# Tile0.net
KiCad netlist of a schematic drawn in Altium Designer
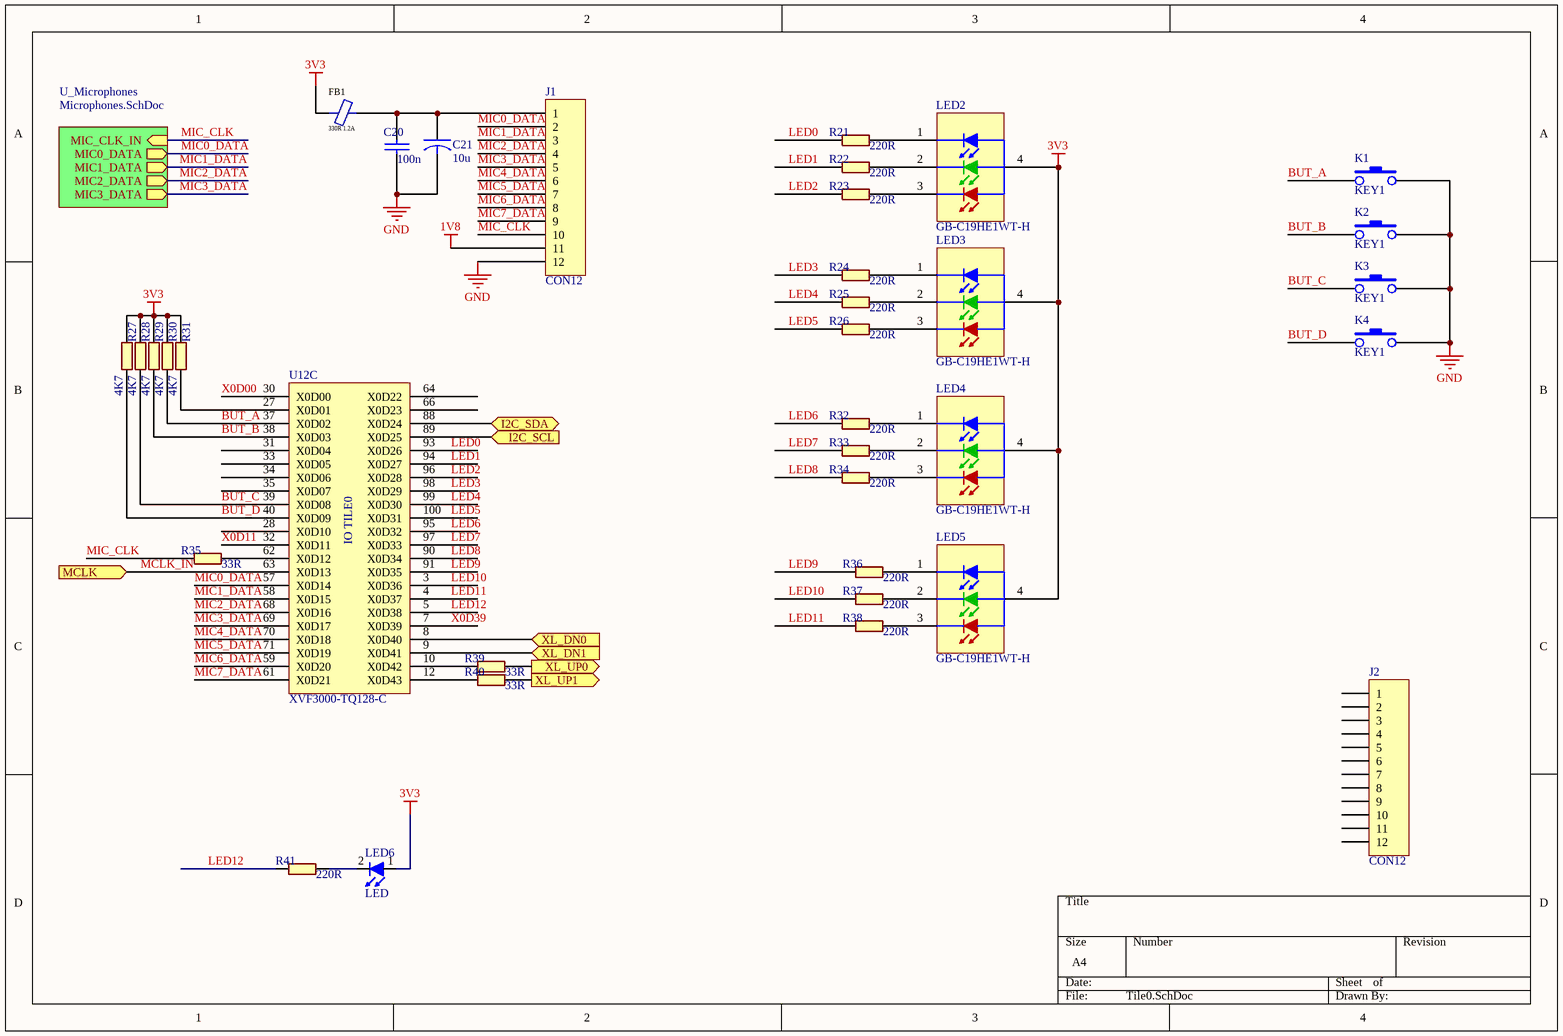
[diagram p0: Tile0.SchDoc]

(export (version "E")
  (design (tool "Eeschema 10.0.6"))
  (components
    (comp (ref "C20")
      (value "100n")
      (footprint "C0603")
      (description "Capacitor")
      (libsource (lib "Library") (part "CAP"))
    )
    (comp (ref "C21")
      (value "10u")
      (footprint "C1206")
      (description "Capacitor")
      (libsource (lib "Library") (part "CAPACITOR"))
    )
    (comp (ref "FB1") (value "330R 1.2A") (footprint "L0603") (libsource (lib "Library") (part "FB")))
    (comp (ref "J1")
      (value "CON12")
      (footprint "FFC/SM0.5-2H12A")
      (description "Connector")
      (libsource (lib "Library") (part "CON12"))
    )
    (comp (ref "J2")
      (value "CON12")
      (footprint "FFC/SM0.5-2H12A")
      (description "Connector")
      (libsource (lib "Library") (part "CON12"))
    )
    (comp (ref "K1")
      (value "KEY1")
      (footprint "BUTTON6")
      (description "BUTTON")
      (libsource (lib "Library") (part "BUTTON"))
    )
    (comp (ref "K2")
      (value "KEY1")
      (footprint "BUTTON6")
      (description "BUTTON")
      (libsource (lib "Library") (part "BUTTON"))
    )
    (comp (ref "K3")
      (value "KEY1")
      (footprint "BUTTON6")
      (description "BUTTON")
      (libsource (lib "Library") (part "BUTTON"))
    )
    (comp (ref "K4")
      (value "KEY1")
      (footprint "BUTTON6")
      (description "BUTTON")
      (libsource (lib "Library") (part "BUTTON"))
    )
    (comp (ref "LED2")
      (value "GB-C19HE1WT-H")
      (footprint "LED1615")
      (description "LED RGB")
      (libsource (lib "Library") (part "LED-1615"))
    )
    (comp (ref "LED3")
      (value "GB-C19HE1WT-H")
      (footprint "LED1615")
      (description "LED RGB")
      (libsource (lib "Library") (part "LED-1615"))
    )
    (comp (ref "LED4")
      (value "GB-C19HE1WT-H")
      (footprint "LED1615")
      (description "LED RGB")
      (libsource (lib "Library") (part "LED-1615"))
    )
    (comp (ref "LED5")
      (value "GB-C19HE1WT-H")
      (footprint "LED1615")
      (description "LED RGB")
      (libsource (lib "Library") (part "LED-1615"))
    )
    (comp (ref "LED6") (value "LED") (footprint "LED0805") (libsource (lib "Library") (part "LED")))
    (comp (ref "R21")
      (value "220R")
      (footprint "R0603")
      (description "RES")
      (libsource (lib "Library") (part "R"))
    )
    (comp (ref "R22")
      (value "220R")
      (footprint "R0603")
      (description "RES")
      (libsource (lib "Library") (part "R"))
    )
    (comp (ref "R23")
      (value "220R")
      (footprint "R0603")
      (description "RES")
      (libsource (lib "Library") (part "R"))
    )
    (comp (ref "R24")
      (value "220R")
      (footprint "R0603")
      (description "RES")
      (libsource (lib "Library") (part "R"))
    )
    (comp (ref "R25")
      (value "220R")
      (footprint "R0603")
      (description "RES")
      (libsource (lib "Library") (part "R"))
    )
    (comp (ref "R26")
      (value "220R")
      (footprint "R0603")
      (description "RES")
      (libsource (lib "Library") (part "R"))
    )
    (comp (ref "R27") (value "4K7") (footprint "R0603") (description "RES") (libsource (lib "") (part "R_1")))
    (comp (ref "R28") (value "4K7") (footprint "R0603") (description "RES") (libsource (lib "") (part "R_1")))
    (comp (ref "R29") (value "4K7") (footprint "R0603") (description "RES") (libsource (lib "") (part "R_1")))
    (comp (ref "R30") (value "4K7") (footprint "R0603") (description "RES") (libsource (lib "") (part "R_1")))
    (comp (ref "R31") (value "4K7") (footprint "R0603") (description "RES") (libsource (lib "") (part "R_1")))
    (comp (ref "R32")
      (value "220R")
      (footprint "R0603")
      (description "RES")
      (libsource (lib "Library") (part "R"))
    )
    (comp (ref "R33")
      (value "220R")
      (footprint "R0603")
      (description "RES")
      (libsource (lib "Library") (part "R"))
    )
    (comp (ref "R34")
      (value "220R")
      (footprint "R0603")
      (description "RES")
      (libsource (lib "Library") (part "R"))
    )
    (comp (ref "R35")
      (value "33R")
      (footprint "R0603")
      (description "RES")
      (libsource (lib "Library") (part "R"))
    )
    (comp (ref "R36")
      (value "220R")
      (footprint "R0603")
      (description "RES")
      (libsource (lib "Library") (part "R"))
    )
    (comp (ref "R37")
      (value "220R")
      (footprint "R0603")
      (description "RES")
      (libsource (lib "Library") (part "R"))
    )
    (comp (ref "R38")
      (value "220R")
      (footprint "R0603")
      (description "RES")
      (libsource (lib "Library") (part "R"))
    )
    (comp (ref "R39")
      (value "33R")
      (footprint "R0603")
      (description "RES")
      (libsource (lib "Library") (part "R"))
    )
    (comp (ref "R40")
      (value "33R")
      (footprint "R0603")
      (description "RES")
      (libsource (lib "Library") (part "R"))
    )
    (comp (ref "R41")
      (value "220R")
      (footprint "R0603")
      (description "RES")
      (libsource (lib "Library") (part "R"))
    )
    (comp (ref "U12")
      (value "XVF3000-TQ128-C")
      (footprint "LQFP-128 - VSS")
      (libsource (lib "Library") (part "XVF3000-TQ128-C"))
    )
  )
  (nets
    (net (code "1") (name "/BUT_A") (class "Default")
      (node (ref "K1") (pin "1") (pinfunction "1_1") (pintype "passive"))
      (node (ref "R30") (pin "1") (pinfunction "1_1") (pintype "passive"))
      (node (ref "U12") (pin "37") (pinfunction "X0D02_37") (pintype "passive"))
    )
    (net (code "2") (name "/BUT_B") (class "Default")
      (node (ref "K2") (pin "1") (pinfunction "1_1") (pintype "passive"))
      (node (ref "R29") (pin "1") (pinfunction "1_1") (pintype "passive"))
      (node (ref "U12") (pin "38") (pinfunction "X0D03_38") (pintype "passive"))
    )
    (net (code "3") (name "/BUT_C") (class "Default")
      (node (ref "K3") (pin "1") (pinfunction "1_1") (pintype "passive"))
      (node (ref "R28") (pin "1") (pinfunction "1_1") (pintype "passive"))
      (node (ref "U12") (pin "39") (pinfunction "X0D08_39") (pintype "passive"))
    )
    (net (code "4") (name "/BUT_D") (class "Default")
      (node (ref "K4") (pin "1") (pinfunction "1_1") (pintype "passive"))
      (node (ref "R27") (pin "1") (pinfunction "1_1") (pintype "passive"))
      (node (ref "U12") (pin "40") (pinfunction "X0D09_40") (pintype "passive"))
    )
    (net (code "5") (name "/I2C_SCL") (class "Default")
      (node (ref "U12") (pin "89") (pinfunction "X0D25_89") (pintype "passive"))
    )
    (net (code "6") (name "/I2C_SDA") (class "Default")
      (node (ref "U12") (pin "88") (pinfunction "X0D24_88") (pintype "passive"))
    )
    (net (code "7") (name "/LED0") (class "Default")
      (node (ref "R21") (pin "2") (pinfunction "2_2") (pintype "passive"))
      (node (ref "U12") (pin "93") (pinfunction "X0D26_93") (pintype "passive"))
    )
    (net (code "8") (name "/LED1") (class "Default")
      (node (ref "R22") (pin "2") (pinfunction "2_2") (pintype "passive"))
      (node (ref "U12") (pin "94") (pinfunction "X0D27_94") (pintype "passive"))
    )
    (net (code "9") (name "/LED2") (class "Default")
      (node (ref "R23") (pin "2") (pinfunction "2_2") (pintype "passive"))
      (node (ref "U12") (pin "96") (pinfunction "X0D28_96") (pintype "passive"))
    )
    (net (code "10") (name "/LED3") (class "Default")
      (node (ref "R24") (pin "2") (pinfunction "2_2") (pintype "passive"))
      (node (ref "U12") (pin "98") (pinfunction "X0D29_98") (pintype "passive"))
    )
    (net (code "11") (name "/LED4") (class "Default")
      (node (ref "R25") (pin "2") (pinfunction "2_2") (pintype "passive"))
      (node (ref "U12") (pin "99") (pinfunction "X0D30_99") (pintype "passive"))
    )
    (net (code "12") (name "/LED5") (class "Default")
      (node (ref "R26") (pin "2") (pinfunction "2_2") (pintype "passive"))
      (node (ref "U12") (pin "100") (pinfunction "X0D31_100") (pintype "passive"))
    )
    (net (code "13") (name "/LED6") (class "Default")
      (node (ref "R32") (pin "2") (pinfunction "2_2") (pintype "passive"))
      (node (ref "U12") (pin "95") (pinfunction "X0D32_95") (pintype "passive"))
    )
    (net (code "14") (name "/LED7") (class "Default")
      (node (ref "R33") (pin "2") (pinfunction "2_2") (pintype "passive"))
      (node (ref "U12") (pin "97") (pinfunction "X0D33_97") (pintype "passive"))
    )
    (net (code "15") (name "/LED8") (class "Default")
      (node (ref "R34") (pin "2") (pinfunction "2_2") (pintype "passive"))
      (node (ref "U12") (pin "90") (pinfunction "X0D34_90") (pintype "passive"))
    )
    (net (code "16") (name "/LED9") (class "Default")
      (node (ref "R36") (pin "2") (pinfunction "2_2") (pintype "passive"))
      (node (ref "U12") (pin "91") (pinfunction "X0D35_91") (pintype "passive"))
    )
    (net (code "17") (name "/LED10") (class "Default")
      (node (ref "R37") (pin "2") (pinfunction "2_2") (pintype "passive"))
      (node (ref "U12") (pin "3") (pinfunction "X0D36_3") (pintype "passive"))
    )
    (net (code "18") (name "/LED11") (class "Default")
      (node (ref "R38") (pin "2") (pinfunction "2_2") (pintype "passive"))
      (node (ref "U12") (pin "4") (pinfunction "X0D37_4") (pintype "passive"))
    )
    (net (code "19") (name "/LED12") (class "Default")
      (node (ref "R41") (pin "2") (pinfunction "2_2") (pintype "passive"))
      (node (ref "U12") (pin "5") (pinfunction "X0D38_5") (pintype "passive"))
    )
    (net (code "20") (name "/MCLK_IN") (class "Default")
      (node (ref "U12") (pin "63") (pinfunction "X0D13_63") (pintype "passive"))
    )
    (net (code "21") (name "/MIC0_DATA") (class "Default")
      (node (ref "J1") (pin "2") (pinfunction "2_2") (pintype "passive"))
      (node (ref "U12") (pin "57") (pinfunction "X0D14_57") (pintype "passive"))
    )
    (net (code "22") (name "/MIC1_DATA") (class "Default")
      (node (ref "J1") (pin "3") (pinfunction "3_3") (pintype "passive"))
      (node (ref "U12") (pin "58") (pinfunction "X0D15_58") (pintype "passive"))
    )
    (net (code "23") (name "/MIC2_DATA") (class "Default")
      (node (ref "J1") (pin "4") (pinfunction "4_4") (pintype "passive"))
      (node (ref "U12") (pin "68") (pinfunction "X0D16_68") (pintype "passive"))
    )
    (net (code "24") (name "/MIC3_DATA") (class "Default")
      (node (ref "J1") (pin "5") (pinfunction "5_5") (pintype "passive"))
      (node (ref "U12") (pin "69") (pinfunction "X0D17_69") (pintype "passive"))
    )
    (net (code "25") (name "/MIC4_DATA") (class "Default")
      (node (ref "J1") (pin "6") (pinfunction "6_6") (pintype "passive"))
      (node (ref "U12") (pin "70") (pinfunction "X0D18_70") (pintype "passive"))
    )
    (net (code "26") (name "/MIC5_DATA") (class "Default")
      (node (ref "J1") (pin "7") (pinfunction "7_7") (pintype "passive"))
      (node (ref "U12") (pin "71") (pinfunction "X0D19_71") (pintype "passive"))
    )
    (net (code "27") (name "/MIC6_DATA") (class "Default")
      (node (ref "J1") (pin "8") (pinfunction "8_8") (pintype "passive"))
      (node (ref "U12") (pin "59") (pinfunction "X0D20_59") (pintype "passive"))
    )
    (net (code "28") (name "/MIC7_DATA") (class "Default")
      (node (ref "J1") (pin "9") (pinfunction "9_9") (pintype "passive"))
      (node (ref "U12") (pin "61") (pinfunction "X0D21_61") (pintype "passive"))
    )
    (net (code "29") (name "/MIC_CLK") (class "Default")
      (node (ref "J1") (pin "10") (pinfunction "10_10") (pintype "passive"))
      (node (ref "R35") (pin "2") (pinfunction "2_2") (pintype "passive"))
    )
    (net (code "30") (name "/X0D00") (class "Default")
      (node (ref "U12") (pin "30") (pinfunction "X0D00_30") (pintype "passive"))
    )
    (net (code "31") (name "/X0D11") (class "Default")
      (node (ref "U12") (pin "32") (pinfunction "X0D11_32") (pintype "passive"))
    )
    (net (code "32") (name "/X0D39") (class "Default")
      (node (ref "U12") (pin "7") (pinfunction "X0D39_7") (pintype "passive"))
    )
    (net (code "33") (name "/XL_DN0") (class "Default")
      (node (ref "U12") (pin "8") (pinfunction "X0D40_8") (pintype "passive"))
    )
    (net (code "34") (name "/XL_DN1") (class "Default")
      (node (ref "U12") (pin "9") (pinfunction "X0D41_9") (pintype "passive"))
    )
    (net (code "35") (name "/XL_UP0") (class "Default")
      (node (ref "R39") (pin "1") (pinfunction "1_1") (pintype "passive"))
    )
    (net (code "36") (name "/XL_UP1") (class "Default")
      (node (ref "R40") (pin "1") (pinfunction "1_1") (pintype "passive"))
    )
    (net (code "37") (name "1V8") (class "Default")
      (node (ref "J1") (pin "11") (pinfunction "11_11") (pintype "passive"))
    )
    (net (code "38") (name "3V3") (class "Default")
      (node (ref "FB1") (pin "2") (pinfunction "2_2") (pintype "power_in"))
      (node (ref "LED2") (pin "4") (pinfunction "4_4") (pintype "passive"))
      (node (ref "LED3") (pin "4") (pinfunction "4_4") (pintype "passive"))
      (node (ref "LED4") (pin "4") (pinfunction "4_4") (pintype "passive"))
      (node (ref "LED5") (pin "4") (pinfunction "4_4") (pintype "passive"))
      (node (ref "LED6") (pin "1") (pinfunction "1_1") (pintype "passive"))
      (node (ref "R27") (pin "2") (pinfunction "2_2") (pintype "passive"))
      (node (ref "R28") (pin "2") (pinfunction "2_2") (pintype "passive"))
      (node (ref "R29") (pin "2") (pinfunction "2_2") (pintype "passive"))
      (node (ref "R30") (pin "2") (pinfunction "2_2") (pintype "passive"))
      (node (ref "R31") (pin "2") (pinfunction "2_2") (pintype "passive"))
    )
    (net (code "39") (name "GND") (class "Default")
      (node (ref "C20") (pin "2") (pinfunction "2_2") (pintype "passive"))
      (node (ref "C21") (pin "2") (pinfunction "2_2") (pintype "passive"))
      (node (ref "J1") (pin "12") (pinfunction "12_12") (pintype "passive"))
      (node (ref "K1") (pin "2") (pinfunction "2_2") (pintype "passive"))
      (node (ref "K2") (pin "2") (pinfunction "2_2") (pintype "passive"))
      (node (ref "K3") (pin "2") (pinfunction "2_2") (pintype "passive"))
      (node (ref "K4") (pin "2") (pinfunction "2_2") (pintype "passive"))
    )
    (net (code "40") (name "Net-(C20-Pad1)") (class "Default")
      (node (ref "C20") (pin "1") (pinfunction "1_1") (pintype "passive"))
      (node (ref "C21") (pin "1") (pinfunction "1_1") (pintype "passive"))
      (node (ref "FB1") (pin "1") (pinfunction "1_1") (pintype "power_in"))
      (node (ref "J1") (pin "1") (pinfunction "1_1") (pintype "passive"))
    )
    (net (code "41") (name "Net-(LED2-Pad1)") (class "Default")
      (node (ref "LED2") (pin "1") (pinfunction "1_1") (pintype "passive"))
      (node (ref "R21") (pin "1") (pinfunction "1_1") (pintype "passive"))
    )
    (net (code "42") (name "Net-(LED2-Pad2)") (class "Default")
      (node (ref "LED2") (pin "2") (pinfunction "2_2") (pintype "passive"))
      (node (ref "R22") (pin "1") (pinfunction "1_1") (pintype "passive"))
    )
    (net (code "43") (name "Net-(LED2-Pad3)") (class "Default")
      (node (ref "LED2") (pin "3") (pinfunction "3_3") (pintype "passive"))
      (node (ref "R23") (pin "1") (pinfunction "1_1") (pintype "passive"))
    )
    (net (code "44") (name "Net-(LED3-Pad1)") (class "Default")
      (node (ref "LED3") (pin "1") (pinfunction "1_1") (pintype "passive"))
      (node (ref "R24") (pin "1") (pinfunction "1_1") (pintype "passive"))
    )
    (net (code "45") (name "Net-(LED3-Pad2)") (class "Default")
      (node (ref "LED3") (pin "2") (pinfunction "2_2") (pintype "passive"))
      (node (ref "R25") (pin "1") (pinfunction "1_1") (pintype "passive"))
    )
    (net (code "46") (name "Net-(LED3-Pad3)") (class "Default")
      (node (ref "LED3") (pin "3") (pinfunction "3_3") (pintype "passive"))
      (node (ref "R26") (pin "1") (pinfunction "1_1") (pintype "passive"))
    )
    (net (code "47") (name "Net-(LED4-Pad1)") (class "Default")
      (node (ref "LED4") (pin "1") (pinfunction "1_1") (pintype "passive"))
      (node (ref "R32") (pin "1") (pinfunction "1_1") (pintype "passive"))
    )
    (net (code "48") (name "Net-(LED4-Pad2)") (class "Default")
      (node (ref "LED4") (pin "2") (pinfunction "2_2") (pintype "passive"))
      (node (ref "R33") (pin "1") (pinfunction "1_1") (pintype "passive"))
    )
    (net (code "49") (name "Net-(LED4-Pad3)") (class "Default")
      (node (ref "LED4") (pin "3") (pinfunction "3_3") (pintype "passive"))
      (node (ref "R34") (pin "1") (pinfunction "1_1") (pintype "passive"))
    )
    (net (code "50") (name "Net-(LED5-Pad1)") (class "Default")
      (node (ref "LED5") (pin "1") (pinfunction "1_1") (pintype "passive"))
      (node (ref "R36") (pin "1") (pinfunction "1_1") (pintype "passive"))
    )
    (net (code "51") (name "Net-(LED5-Pad2)") (class "Default")
      (node (ref "LED5") (pin "2") (pinfunction "2_2") (pintype "passive"))
      (node (ref "R37") (pin "1") (pinfunction "1_1") (pintype "passive"))
    )
    (net (code "52") (name "Net-(LED5-Pad3)") (class "Default")
      (node (ref "LED5") (pin "3") (pinfunction "3_3") (pintype "passive"))
      (node (ref "R38") (pin "1") (pinfunction "1_1") (pintype "passive"))
    )
    (net (code "53") (name "Net-(LED6-Pad2)") (class "Default")
      (node (ref "LED6") (pin "2") (pinfunction "2_2") (pintype "passive"))
      (node (ref "R41") (pin "1") (pinfunction "1_1") (pintype "passive"))
    )
    (net (code "54") (name "Net-(U12C-X0D01)") (class "Default")
      (node (ref "R31") (pin "1") (pinfunction "1_1") (pintype "passive"))
      (node (ref "U12") (pin "27") (pinfunction "X0D01_27") (pintype "passive"))
    )
    (net (code "55") (name "Net-(U12C-X0D12)") (class "Default")
      (node (ref "R35") (pin "1") (pinfunction "1_1") (pintype "passive"))
      (node (ref "U12") (pin "62") (pinfunction "X0D12_62") (pintype "passive"))
    )
    (net (code "56") (name "Net-(U12C-X0D42)") (class "Default")
      (node (ref "R39") (pin "2") (pinfunction "2_2") (pintype "passive"))
      (node (ref "U12") (pin "10") (pinfunction "X0D42_10") (pintype "passive"))
    )
    (net (code "57") (name "Net-(U12C-X0D43)") (class "Default")
      (node (ref "R40") (pin "2") (pinfunction "2_2") (pintype "passive"))
      (node (ref "U12") (pin "12") (pinfunction "X0D43_12") (pintype "passive"))
    )
    (net (code "58") (name "unconnected-(J2-Pad1)") (class "Default")
      (node (ref "J2") (pin "1") (pinfunction "1_1") (pintype "passive"))
    )
    (net (code "59") (name "unconnected-(J2-Pad2)") (class "Default")
      (node (ref "J2") (pin "2") (pinfunction "2_2") (pintype "passive"))
    )
    (net (code "60") (name "unconnected-(J2-Pad3)") (class "Default")
      (node (ref "J2") (pin "3") (pinfunction "3_3") (pintype "passive"))
    )
    (net (code "61") (name "unconnected-(J2-Pad4)") (class "Default")
      (node (ref "J2") (pin "4") (pinfunction "4_4") (pintype "passive"))
    )
    (net (code "62") (name "unconnected-(J2-Pad5)") (class "Default")
      (node (ref "J2") (pin "5") (pinfunction "5_5") (pintype "passive"))
    )
    (net (code "63") (name "unconnected-(J2-Pad6)") (class "Default")
      (node (ref "J2") (pin "6") (pinfunction "6_6") (pintype "passive"))
    )
    (net (code "64") (name "unconnected-(J2-Pad7)") (class "Default")
      (node (ref "J2") (pin "7") (pinfunction "7_7") (pintype "passive"))
    )
    (net (code "65") (name "unconnected-(J2-Pad8)") (class "Default")
      (node (ref "J2") (pin "8") (pinfunction "8_8") (pintype "passive"))
    )
    (net (code "66") (name "unconnected-(J2-Pad9)") (class "Default")
      (node (ref "J2") (pin "9") (pinfunction "9_9") (pintype "passive"))
    )
    (net (code "67") (name "unconnected-(J2-Pad10)") (class "Default")
      (node (ref "J2") (pin "10") (pinfunction "10_10") (pintype "passive"))
    )
    (net (code "68") (name "unconnected-(J2-Pad11)") (class "Default")
      (node (ref "J2") (pin "11") (pinfunction "11_11") (pintype "passive"))
    )
    (net (code "69") (name "unconnected-(J2-Pad12)") (class "Default")
      (node (ref "J2") (pin "12") (pinfunction "12_12") (pintype "passive"))
    )
    (net (code "70") (name "unconnected-(U12C-X0D04-Pad31)") (class "Default")
      (node (ref "U12") (pin "31") (pinfunction "X0D04_31") (pintype "passive"))
    )
    (net (code "71") (name "unconnected-(U12C-X0D05-Pad33)") (class "Default")
      (node (ref "U12") (pin "33") (pinfunction "X0D05_33") (pintype "passive"))
    )
    (net (code "72") (name "unconnected-(U12C-X0D06-Pad34)") (class "Default")
      (node (ref "U12") (pin "34") (pinfunction "X0D06_34") (pintype "passive"))
    )
    (net (code "73") (name "unconnected-(U12C-X0D07-Pad35)") (class "Default")
      (node (ref "U12") (pin "35") (pinfunction "X0D07_35") (pintype "passive"))
    )
    (net (code "74") (name "unconnected-(U12C-X0D10-Pad28)") (class "Default")
      (node (ref "U12") (pin "28") (pinfunction "X0D10_28") (pintype "passive"))
    )
    (net (code "75") (name "unconnected-(U12C-X0D22-Pad64)") (class "Default")
      (node (ref "U12") (pin "64") (pinfunction "X0D22_64") (pintype "passive"))
    )
    (net (code "76") (name "unconnected-(U12C-X0D23-Pad66)") (class "Default")
      (node (ref "U12") (pin "66") (pinfunction "X0D23_66") (pintype "passive"))
    )
  )
)
